# LOGIC_FPGA.net
KiCad netlist of a schematic drawn in Altium Designer
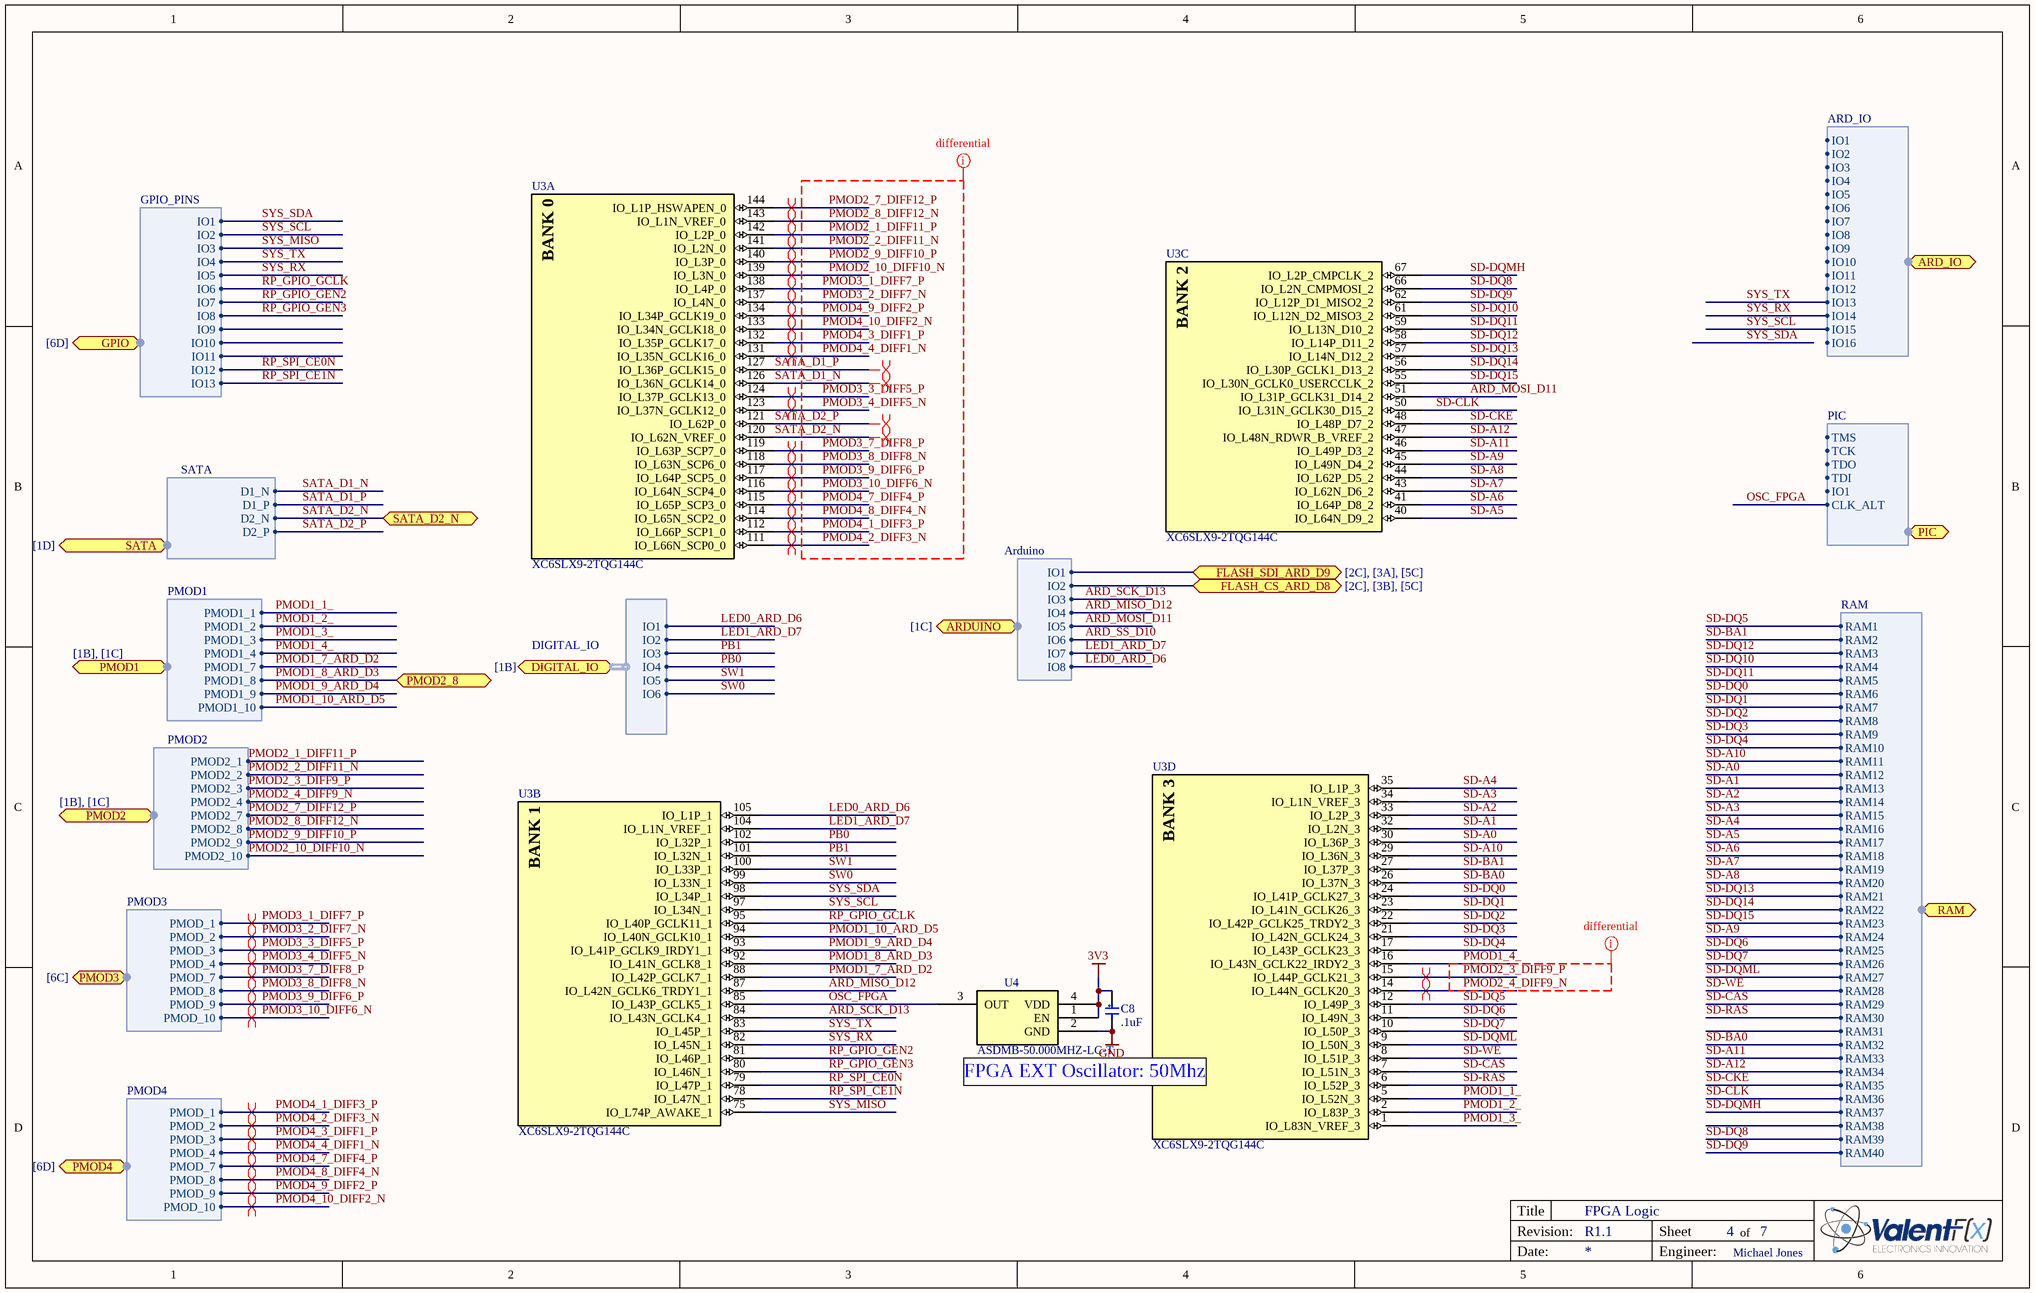
[diagram p0: LOGIC_FPGA.SchDoc]

(export (version "E")
  (design (tool "Eeschema 10.0.6"))
  (components
    (comp (ref "C8")
      (value ".1uF")
      (footprint "c0603")
      (description "CAP CER 0.1UF 25V Y5V 0603")
      (fields
        (field (name "MANUFACTURER") "Samsung Electro-Mechanics America, Inc")
        (field (name "MANUFACTURER PART NUMBER") "CL10F104ZA8NNNC")
      )
      (libsource (lib "mCapacitors") (part "C0603 - CL10F104ZA8NNNC"))
    )
    (comp (ref "U3")
      (value "XC6SLX9-2TQG144C")
      (footprint "TQ144_L")
      (description "IC FPAG SPARTAN 6 9K 144TQFP")
      (fields (field (name "MANUFACTURER") "Xilinx Inc"))
      (libsource (lib "mIC") (part "FPGA - XC6SLX9-2TQG144C"))
    )
    (comp (ref "U4")
      (value "ASDMB-50.000MHZ-LC-T")
      (footprint "ASDMB - osc")
      (description "OSC MEMS 50.000 MHZ SMD")
      (fields (field (name "MANUFACTURER") "Abracon Corporation"))
      (libsource (lib "eIC") (part "ASDMB-50.000MHZ-LC-T"))
    )
  )
  (nets
    (net (code "12") (name "/ARD_MISO_D12") (class "Default")
      (node (ref "U3") (pin "87") (pinfunction "IO_L42N_GCLK6_TRDY1_1_87") (pintype "bidirectional"))
    )
    (net (code "13") (name "/ARD_MOSI_D11") (class "Default")
      (node (ref "U3") (pin "51") (pinfunction "IO_L31P_GCLK31_D14_2_51") (pintype "bidirectional"))
    )
    (net (code "14") (name "/ARD_SCK_D13") (class "Default")
      (node (ref "U3") (pin "84") (pinfunction "IO_L43N_GCLK4_1_84") (pintype "bidirectional"))
    )
    (net (code "18") (name "/LED0_ARD_D6") (class "Default")
      (node (ref "U3") (pin "105") (pinfunction "IO_L1P_1_105") (pintype "bidirectional"))
    )
    (net (code "19") (name "/LED1_ARD_D7") (class "Default")
      (node (ref "U3") (pin "104") (pinfunction "IO_L1N_VREF_1_104") (pintype "bidirectional"))
    )
    (net (code "20") (name "/OSC_FPGA") (class "Default")
      (node (ref "U3") (pin "85") (pinfunction "IO_L43P_GCLK5_1_85") (pintype "bidirectional"))
      (node (ref "U4") (pin "3") (pinfunction "OUT_3") (pintype "passive"))
    )
    (net (code "21") (name "/PB0") (class "Default")
      (node (ref "U3") (pin "102") (pinfunction "IO_L32P_1_102") (pintype "bidirectional"))
    )
    (net (code "22") (name "/PB1") (class "Default")
      (node (ref "U3") (pin "101") (pinfunction "IO_L32N_1_101") (pintype "bidirectional"))
    )
    (net (code "23") (name "/PMOD1_1_") (class "Default")
      (node (ref "U3") (pin "5") (pinfunction "IO_L52N_3_5") (pintype "bidirectional"))
    )
    (net (code "24") (name "/PMOD1_2_") (class "Default")
      (node (ref "U3") (pin "2") (pinfunction "IO_L83P_3_2") (pintype "bidirectional"))
    )
    (net (code "25") (name "/PMOD1_3_") (class "Default")
      (node (ref "U3") (pin "1") (pinfunction "IO_L83N_VREF_3_1") (pintype "bidirectional"))
    )
    (net (code "26") (name "/PMOD1_4_") (class "Default")
      (node (ref "U3") (pin "16") (pinfunction "IO_L43N_GCLK22_IRDY2_3_16") (pintype "bidirectional"))
    )
    (net (code "27") (name "/PMOD1_7_ARD_D2") (class "Default")
      (node (ref "U3") (pin "88") (pinfunction "IO_L42P_GCLK7_1_88") (pintype "bidirectional"))
    )
    (net (code "28") (name "/PMOD1_8_ARD_D3") (class "Default")
      (node (ref "U3") (pin "92") (pinfunction "IO_L41N_GCLK8_1_92") (pintype "bidirectional"))
    )
    (net (code "29") (name "/PMOD1_9_ARD_D4") (class "Default")
      (node (ref "U3") (pin "93") (pinfunction "IO_L41P_GCLK9_IRDY1_1_93") (pintype "bidirectional"))
    )
    (net (code "30") (name "/PMOD1_10_ARD_D5") (class "Default")
      (node (ref "U3") (pin "94") (pinfunction "IO_L40N_GCLK10_1_94") (pintype "bidirectional"))
    )
    (net (code "31") (name "/PMOD2_1_DIFF11_P") (class "Default")
      (node (ref "U3") (pin "142") (pinfunction "IO_L2P_0_142") (pintype "bidirectional"))
    )
    (net (code "32") (name "/PMOD2_2_DIFF11_N") (class "Default")
      (node (ref "U3") (pin "141") (pinfunction "IO_L2N_0_141") (pintype "bidirectional"))
    )
    (net (code "33") (name "/PMOD2_3_DIFF9_P") (class "Default")
      (node (ref "U3") (pin "15") (pinfunction "IO_L44P_GCLK21_3_15") (pintype "bidirectional"))
    )
    (net (code "34") (name "/PMOD2_4_DIFF9_N") (class "Default")
      (node (ref "U3") (pin "14") (pinfunction "IO_L44N_GCLK20_3_14") (pintype "bidirectional"))
    )
    (net (code "35") (name "/PMOD2_7_DIFF12_P") (class "Default")
      (node (ref "U3") (pin "144") (pinfunction "IO_L1P_HSWAPEN_0_144") (pintype "bidirectional"))
    )
    (net (code "36") (name "/PMOD2_8_DIFF12_N") (class "Default")
      (node (ref "U3") (pin "143") (pinfunction "IO_L1N_VREF_0_143") (pintype "bidirectional"))
    )
    (net (code "37") (name "/PMOD2_9_DIFF10_P") (class "Default")
      (node (ref "U3") (pin "140") (pinfunction "IO_L3P_0_140") (pintype "bidirectional"))
    )
    (net (code "38") (name "/PMOD2_10_DIFF10_N") (class "Default")
      (node (ref "U3") (pin "139") (pinfunction "IO_L3N_0_139") (pintype "bidirectional"))
    )
    (net (code "39") (name "/PMOD3_1_DIFF7_P") (class "Default")
      (node (ref "U3") (pin "138") (pinfunction "IO_L4P_0_138") (pintype "bidirectional"))
    )
    (net (code "40") (name "/PMOD3_2_DIFF7_N") (class "Default")
      (node (ref "U3") (pin "137") (pinfunction "IO_L4N_0_137") (pintype "bidirectional"))
    )
    (net (code "41") (name "/PMOD3_3_DIFF5_P") (class "Default")
      (node (ref "U3") (pin "124") (pinfunction "IO_L37P_GCLK13_0_124") (pintype "bidirectional"))
    )
    (net (code "42") (name "/PMOD3_4_DIFF5_N") (class "Default")
      (node (ref "U3") (pin "123") (pinfunction "IO_L37N_GCLK12_0_123") (pintype "bidirectional"))
    )
    (net (code "43") (name "/PMOD3_7_DIFF8_P") (class "Default")
      (node (ref "U3") (pin "119") (pinfunction "IO_L63P_SCP7_0_119") (pintype "bidirectional"))
    )
    (net (code "44") (name "/PMOD3_8_DIFF8_N") (class "Default")
      (node (ref "U3") (pin "118") (pinfunction "IO_L63N_SCP6_0_118") (pintype "bidirectional"))
    )
    (net (code "45") (name "/PMOD3_9_DIFF6_P") (class "Default")
      (node (ref "U3") (pin "117") (pinfunction "IO_L64P_SCP5_0_117") (pintype "bidirectional"))
    )
    (net (code "46") (name "/PMOD3_10_DIFF6_N") (class "Default")
      (node (ref "U3") (pin "116") (pinfunction "IO_L64N_SCP4_0_116") (pintype "bidirectional"))
    )
    (net (code "47") (name "/PMOD4_1_DIFF3_P") (class "Default")
      (node (ref "U3") (pin "112") (pinfunction "IO_L66P_SCP1_0_112") (pintype "bidirectional"))
    )
    (net (code "48") (name "/PMOD4_2_DIFF3_N") (class "Default")
      (node (ref "U3") (pin "111") (pinfunction "IO_L66N_SCP0_0_111") (pintype "bidirectional"))
    )
    (net (code "49") (name "/PMOD4_3_DIFF1_P") (class "Default")
      (node (ref "U3") (pin "132") (pinfunction "IO_L35P_GCLK17_0_132") (pintype "bidirectional"))
    )
    (net (code "50") (name "/PMOD4_4_DIFF1_N") (class "Default")
      (node (ref "U3") (pin "131") (pinfunction "IO_L35N_GCLK16_0_131") (pintype "bidirectional"))
    )
    (net (code "51") (name "/PMOD4_7_DIFF4_P") (class "Default")
      (node (ref "U3") (pin "115") (pinfunction "IO_L65P_SCP3_0_115") (pintype "bidirectional"))
    )
    (net (code "52") (name "/PMOD4_8_DIFF4_N") (class "Default")
      (node (ref "U3") (pin "114") (pinfunction "IO_L65N_SCP2_0_114") (pintype "bidirectional"))
    )
    (net (code "53") (name "/PMOD4_9_DIFF2_P") (class "Default")
      (node (ref "U3") (pin "134") (pinfunction "IO_L34P_GCLK19_0_134") (pintype "bidirectional"))
    )
    (net (code "54") (name "/PMOD4_10_DIFF2_N") (class "Default")
      (node (ref "U3") (pin "133") (pinfunction "IO_L34N_GCLK18_0_133") (pintype "bidirectional"))
    )
    (net (code "55") (name "/RP_GPIO_GCLK") (class "Default")
      (node (ref "U3") (pin "95") (pinfunction "IO_L40P_GCLK11_1_95") (pintype "bidirectional"))
    )
    (net (code "56") (name "/RP_GPIO_GEN2") (class "Default")
      (node (ref "U3") (pin "81") (pinfunction "IO_L46P_1_81") (pintype "bidirectional"))
    )
    (net (code "57") (name "/RP_GPIO_GEN3") (class "Default")
      (node (ref "U3") (pin "80") (pinfunction "IO_L46N_1_80") (pintype "bidirectional"))
    )
    (net (code "58") (name "/RP_SPI_CE0N") (class "Default")
      (node (ref "U3") (pin "79") (pinfunction "IO_L47P_1_79") (pintype "bidirectional"))
    )
    (net (code "59") (name "/RP_SPI_CE1N") (class "Default")
      (node (ref "U3") (pin "78") (pinfunction "IO_L47N_1_78") (pintype "bidirectional"))
    )
    (net (code "60") (name "/SATA_D1_N") (class "Default")
      (node (ref "U3") (pin "126") (pinfunction "IO_L36N_GCLK14_0_126") (pintype "bidirectional"))
    )
    (net (code "61") (name "/SATA_D1_P") (class "Default")
      (node (ref "U3") (pin "127") (pinfunction "IO_L36P_GCLK15_0_127") (pintype "bidirectional"))
    )
    (net (code "62") (name "/SATA_D2_N") (class "Default")
      (node (ref "U3") (pin "120") (pinfunction "IO_L62N_VREF_0_120") (pintype "bidirectional"))
    )
    (net (code "63") (name "/SATA_D2_P") (class "Default")
      (node (ref "U3") (pin "121") (pinfunction "IO_L62P_0_121") (pintype "bidirectional"))
    )
    (net (code "64") (name "/SD-A0") (class "Default")
      (node (ref "U3") (pin "30") (pinfunction "IO_L36P_3_30") (pintype "bidirectional"))
    )
    (net (code "65") (name "/SD-A1") (class "Default")
      (node (ref "U3") (pin "32") (pinfunction "IO_L2N_3_32") (pintype "bidirectional"))
    )
    (net (code "66") (name "/SD-A2") (class "Default")
      (node (ref "U3") (pin "33") (pinfunction "IO_L2P_3_33") (pintype "bidirectional"))
    )
    (net (code "67") (name "/SD-A3") (class "Default")
      (node (ref "U3") (pin "34") (pinfunction "IO_L1N_VREF_3_34") (pintype "bidirectional"))
    )
    (net (code "68") (name "/SD-A4") (class "Default")
      (node (ref "U3") (pin "35") (pinfunction "IO_L1P_3_35") (pintype "bidirectional"))
    )
    (net (code "69") (name "/SD-A5") (class "Default")
      (node (ref "U3") (pin "40") (pinfunction "IO_L64N_D9_2_40") (pintype "bidirectional"))
    )
    (net (code "70") (name "/SD-A6") (class "Default")
      (node (ref "U3") (pin "41") (pinfunction "IO_L64P_D8_2_41") (pintype "bidirectional"))
    )
    (net (code "71") (name "/SD-A7") (class "Default")
      (node (ref "U3") (pin "43") (pinfunction "IO_L62N_D6_2_43") (pintype "bidirectional"))
    )
    (net (code "72") (name "/SD-A8") (class "Default")
      (node (ref "U3") (pin "44") (pinfunction "IO_L62P_D5_2_44") (pintype "bidirectional"))
    )
    (net (code "73") (name "/SD-A9") (class "Default")
      (node (ref "U3") (pin "45") (pinfunction "IO_L49N_D4_2_45") (pintype "bidirectional"))
    )
    (net (code "74") (name "/SD-A10") (class "Default")
      (node (ref "U3") (pin "29") (pinfunction "IO_L36N_3_29") (pintype "bidirectional"))
    )
    (net (code "75") (name "/SD-A11") (class "Default")
      (node (ref "U3") (pin "46") (pinfunction "IO_L49P_D3_2_46") (pintype "bidirectional"))
    )
    (net (code "76") (name "/SD-A12") (class "Default")
      (node (ref "U3") (pin "47") (pinfunction "IO_L48N_RDWR_B_VREF_2_47") (pintype "bidirectional"))
    )
    (net (code "77") (name "/SD-BA0") (class "Default")
      (node (ref "U3") (pin "26") (pinfunction "IO_L37N_3_26") (pintype "bidirectional"))
    )
    (net (code "78") (name "/SD-BA1") (class "Default")
      (node (ref "U3") (pin "27") (pinfunction "IO_L37P_3_27") (pintype "bidirectional"))
    )
    (net (code "79") (name "/SD-CAS") (class "Default")
      (node (ref "U3") (pin "7") (pinfunction "IO_L51N_3_7") (pintype "bidirectional"))
    )
    (net (code "80") (name "/SD-CKE") (class "Default")
      (node (ref "U3") (pin "48") (pinfunction "IO_L48P_D7_2_48") (pintype "bidirectional"))
    )
    (net (code "81") (name "/SD-CLK") (class "Default")
      (node (ref "U3") (pin "50") (pinfunction "IO_L31N_GCLK30_D15_2_50") (pintype "bidirectional"))
    )
    (net (code "82") (name "/SD-DQ0") (class "Default")
      (node (ref "U3") (pin "24") (pinfunction "IO_L41P_GCLK27_3_24") (pintype "bidirectional"))
    )
    (net (code "83") (name "/SD-DQ1") (class "Default")
      (node (ref "U3") (pin "23") (pinfunction "IO_L41N_GCLK26_3_23") (pintype "bidirectional"))
    )
    (net (code "84") (name "/SD-DQ2") (class "Default")
      (node (ref "U3") (pin "22") (pinfunction "IO_L42P_GCLK25_TRDY2_3_22") (pintype "bidirectional"))
    )
    (net (code "85") (name "/SD-DQ3") (class "Default")
      (node (ref "U3") (pin "21") (pinfunction "IO_L42N_GCLK24_3_21") (pintype "bidirectional"))
    )
    (net (code "86") (name "/SD-DQ4") (class "Default")
      (node (ref "U3") (pin "17") (pinfunction "IO_L43P_GCLK23_3_17") (pintype "bidirectional"))
    )
    (net (code "87") (name "/SD-DQ5") (class "Default")
      (node (ref "U3") (pin "12") (pinfunction "IO_L49P_3_12") (pintype "bidirectional"))
    )
    (net (code "88") (name "/SD-DQ6") (class "Default")
      (node (ref "U3") (pin "11") (pinfunction "IO_L49N_3_11") (pintype "bidirectional"))
    )
    (net (code "89") (name "/SD-DQ7") (class "Default")
      (node (ref "U3") (pin "10") (pinfunction "IO_L50P_3_10") (pintype "bidirectional"))
    )
    (net (code "90") (name "/SD-DQ8") (class "Default")
      (node (ref "U3") (pin "66") (pinfunction "IO_L2N_CMPMOSI_2_66") (pintype "bidirectional"))
    )
    (net (code "91") (name "/SD-DQ9") (class "Default")
      (node (ref "U3") (pin "62") (pinfunction "IO_L12P_D1_MISO2_2_62") (pintype "bidirectional"))
    )
    (net (code "92") (name "/SD-DQ10") (class "Default")
      (node (ref "U3") (pin "61") (pinfunction "IO_L12N_D2_MISO3_2_61") (pintype "bidirectional"))
    )
    (net (code "93") (name "/SD-DQ11") (class "Default")
      (node (ref "U3") (pin "59") (pinfunction "IO_L13N_D10_2_59") (pintype "bidirectional"))
    )
    (net (code "94") (name "/SD-DQ12") (class "Default")
      (node (ref "U3") (pin "58") (pinfunction "IO_L14P_D11_2_58") (pintype "bidirectional"))
    )
    (net (code "95") (name "/SD-DQ13") (class "Default")
      (node (ref "U3") (pin "57") (pinfunction "IO_L14N_D12_2_57") (pintype "bidirectional"))
    )
    (net (code "96") (name "/SD-DQ14") (class "Default")
      (node (ref "U3") (pin "56") (pinfunction "IO_L30P_GCLK1_D13_2_56") (pintype "bidirectional"))
    )
    (net (code "97") (name "/SD-DQ15") (class "Default")
      (node (ref "U3") (pin "55") (pinfunction "IO_L30N_GCLK0_USERCCLK_2_55") (pintype "bidirectional"))
    )
    (net (code "98") (name "/SD-DQMH") (class "Default")
      (node (ref "U3") (pin "67") (pinfunction "IO_L2P_CMPCLK_2_67") (pintype "bidirectional"))
    )
    (net (code "99") (name "/SD-DQML") (class "Default")
      (node (ref "U3") (pin "9") (pinfunction "IO_L50N_3_9") (pintype "bidirectional"))
    )
    (net (code "100") (name "/SD-RAS") (class "Default")
      (node (ref "U3") (pin "6") (pinfunction "IO_L52P_3_6") (pintype "bidirectional"))
    )
    (net (code "101") (name "/SD-WE") (class "Default")
      (node (ref "U3") (pin "8") (pinfunction "IO_L51P_3_8") (pintype "bidirectional"))
    )
    (net (code "102") (name "/SW0") (class "Default")
      (node (ref "U3") (pin "99") (pinfunction "IO_L33N_1_99") (pintype "bidirectional"))
    )
    (net (code "103") (name "/SW1") (class "Default")
      (node (ref "U3") (pin "100") (pinfunction "IO_L33P_1_100") (pintype "bidirectional"))
    )
    (net (code "104") (name "/SYS_MISO") (class "Default")
      (node (ref "U3") (pin "75") (pinfunction "IO_L74P_AWAKE_1_75") (pintype "bidirectional"))
    )
    (net (code "105") (name "/SYS_RX") (class "Default")
      (node (ref "U3") (pin "82") (pinfunction "IO_L45N_1_82") (pintype "bidirectional"))
    )
    (net (code "106") (name "/SYS_SCL") (class "Default")
      (node (ref "U3") (pin "97") (pinfunction "IO_L34N_1_97") (pintype "bidirectional"))
    )
    (net (code "107") (name "/SYS_SDA") (class "Default")
      (node (ref "U3") (pin "98") (pinfunction "IO_L34P_1_98") (pintype "bidirectional"))
    )
    (net (code "108") (name "/SYS_TX") (class "Default")
      (node (ref "U3") (pin "83") (pinfunction "IO_L45P_1_83") (pintype "bidirectional"))
    )
    (net (code "120") (name "3V3") (class "Default")
      (node (ref "C8") (pin "1") (pinfunction "1_1") (pintype "passive"))
      (node (ref "U4") (pin "1") (pinfunction "EN_1") (pintype "passive"))
      (node (ref "U4") (pin "4") (pinfunction "VDD_4") (pintype "passive"))
    )
    (net (code "121") (name "GND") (class "Default")
      (node (ref "C8") (pin "2") (pinfunction "2_2") (pintype "passive"))
      (node (ref "U4") (pin "2") (pinfunction "GND_2") (pintype "passive"))
    )
  )
)
